# Arduino_S3v3_R3_ftdi.net
KiCad netlist of a schematic drawn in EAGLE
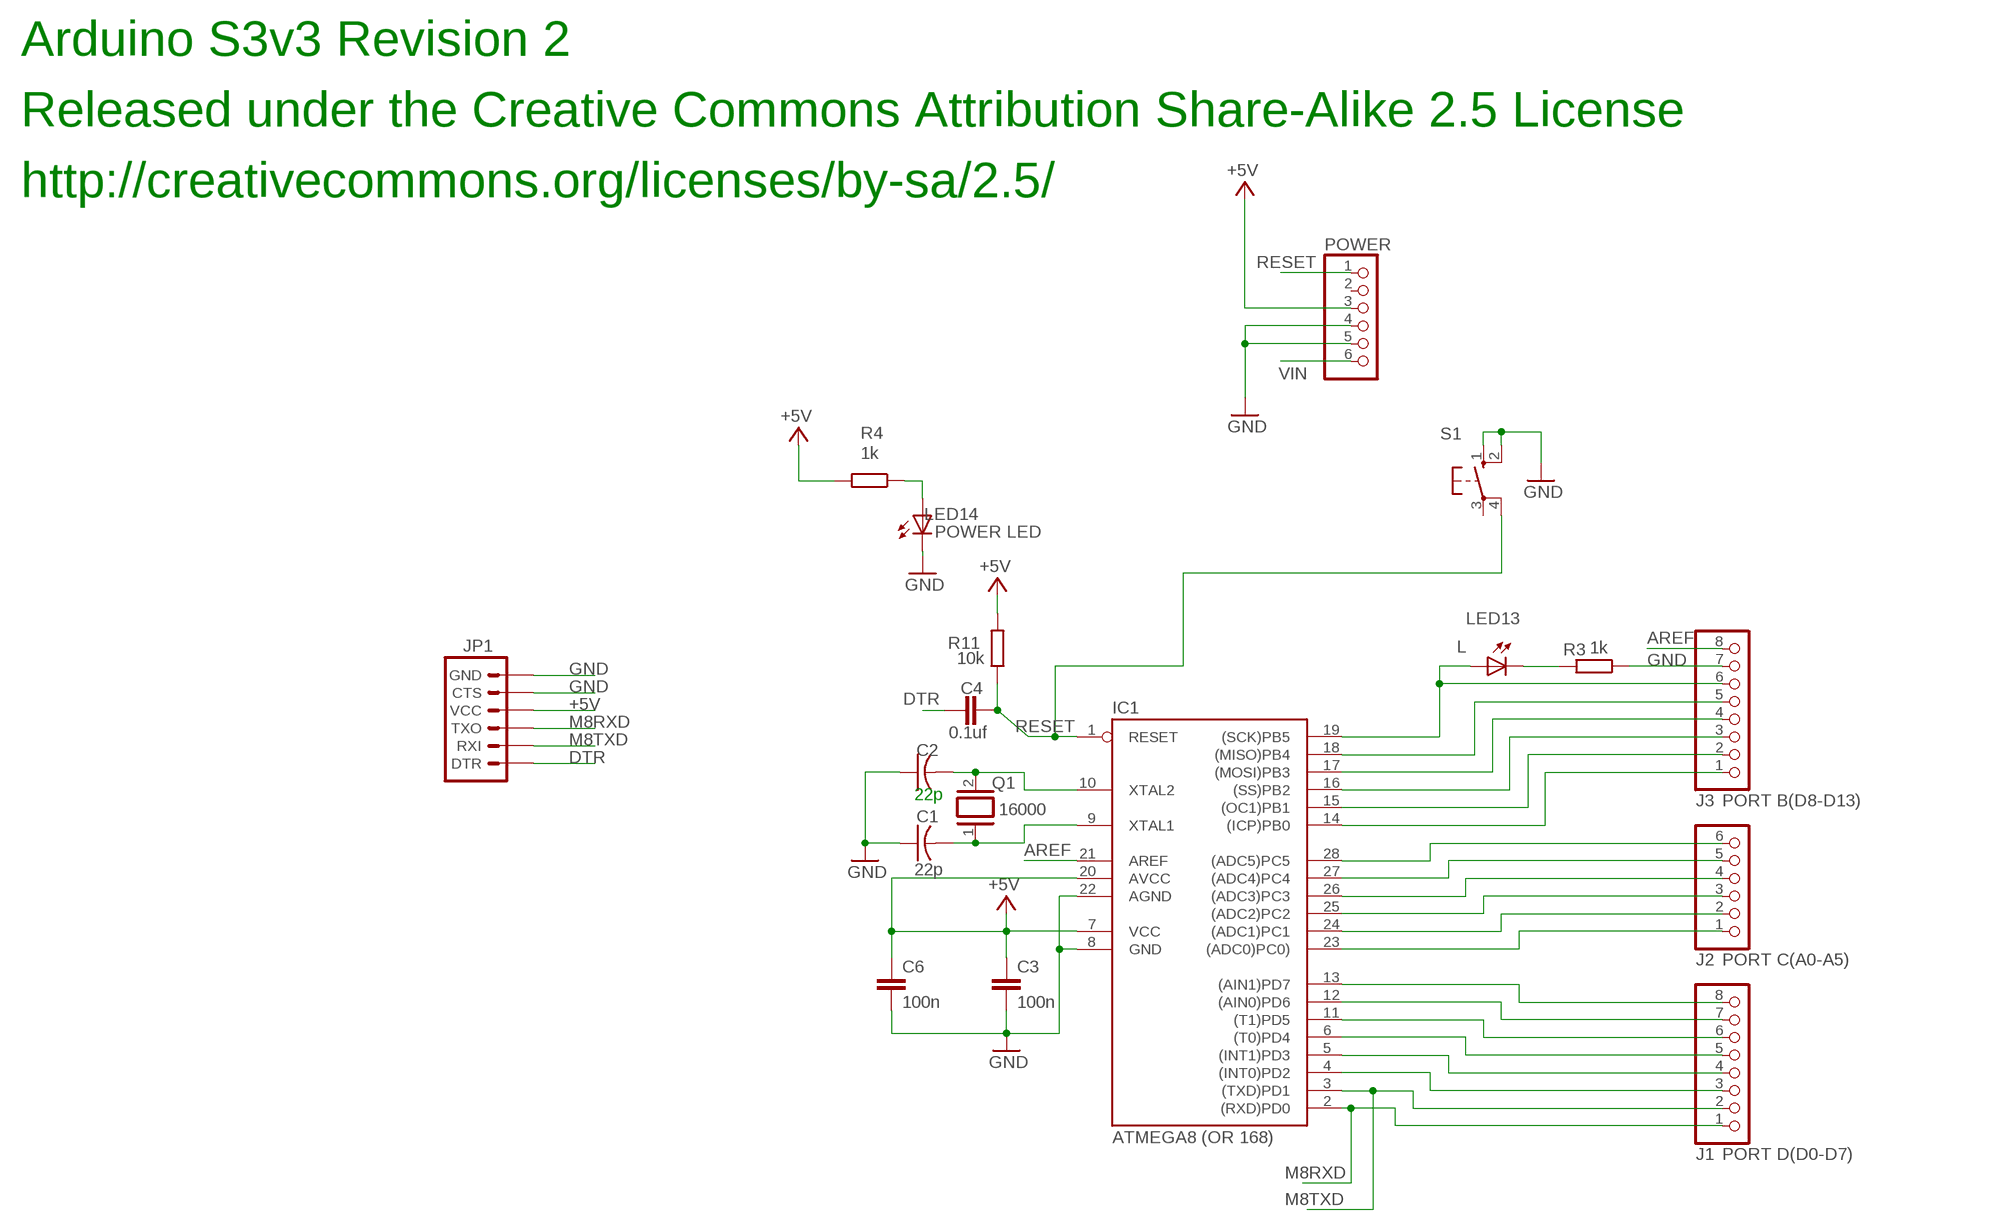
[diagram p0: schematic, sheet 1]

(export (version "E")
  (design (tool "Eeschema 10.0.6"))
  (components
    (comp (ref "C1")
      (value "22p")
      (footprint "eagle-import:C025-024X044")
      (libsource (lib "eagle-import") (part "C-US025-024X044"))
    )
    (comp (ref "C2")
      (value "22p")
      (footprint "eagle-import:C025-024X044")
      (libsource (lib "eagle-import") (part "C-US025-024X044"))
    )
    (comp (ref "C3")
      (value "100n")
      (footprint "eagle-import:C050-025X075")
      (libsource (lib "eagle-import") (part "C-EU050-025X075"))
    )
    (comp (ref "C4")
      (value "0.1uf")
      (footprint "eagle-import:C050-025X075")
      (libsource (lib "eagle-import") (part "C-EU050-025X075"))
    )
    (comp (ref "C6")
      (value "100n")
      (footprint "eagle-import:C050-025X075")
      (libsource (lib "eagle-import") (part "C-EU050-025X075"))
    )
    (comp (ref "IC1")
      (value "ATMEGA8 (OR 168)")
      (footprint "eagle-import:DIL28-3")
      (libsource (lib "eagle-import") (part "AT90S4433P"))
    )
    (comp (ref "J1")
      (value "PORT D(D0-D7)")
      (footprint "eagle-import:1X08")
      (libsource (lib "eagle-import") (part "PINHD-1X8"))
    )
    (comp (ref "J2")
      (value "PORT C(A0-A5)")
      (footprint "eagle-import:1X06")
      (libsource (lib "eagle-import") (part "PINHD-1X6"))
    )
    (comp (ref "J3")
      (value "PORT B(D8-D13)")
      (footprint "eagle-import:1X08")
      (libsource (lib "eagle-import") (part "PINHD-1X8"))
    )
    (comp (ref "JP1")
      (value "ARDUINO_SERIAL_PROGRAMLONGPADS")
      (footprint "eagle-import:1X06_LONGPADS")
      (libsource (lib "eagle-import") (part "ARDUINO_SERIAL_PROGRAMLONGPADS"))
    )
    (comp (ref "LED13")
      (value "L")
      (footprint "eagle-import:LED3MM")
      (libsource (lib "eagle-import") (part "LED3MM"))
    )
    (comp (ref "LED14")
      (value "POWER LED")
      (footprint "eagle-import:LED3MM")
      (libsource (lib "eagle-import") (part "LED3MM"))
    )
    (comp (ref "POWER")
      (value "PINHD-1X6")
      (footprint "eagle-import:1X06")
      (libsource (lib "eagle-import") (part "PINHD-1X6"))
    )
    (comp (ref "Q1")
      (value "16000")
      (footprint "eagle-import:QS")
      (libsource (lib "eagle-import") (part "XTAL/S"))
    )
    (comp (ref "R3")
      (value "1k")
      (footprint "eagle-import:0207_10")
      (libsource (lib "eagle-import") (part "R-EU_0207/10"))
    )
    (comp (ref "R4")
      (value "1k")
      (footprint "eagle-import:0207_10")
      (libsource (lib "eagle-import") (part "R-EU_0207/10"))
    )
    (comp (ref "R11")
      (value "10k")
      (footprint "eagle-import:0207_10")
      (libsource (lib "eagle-import") (part "R-EU_0207/10"))
    )
    (comp (ref "S1")
      (value "10-XX")
      (footprint "eagle-import:B3F-10XX")
      (libsource (lib "eagle-import") (part "10-XX"))
    )
  )
  (nets
    (net (code "1") (name "+5V") (class "Default")
      (node (ref "C3") (pin "1") (pinfunction "1_1") (pintype "passive"))
      (node (ref "C6") (pin "1") (pinfunction "1_1") (pintype "passive"))
      (node (ref "IC1") (pin "20") (pinfunction "AVCC_20") (pintype "power_in"))
      (node (ref "IC1") (pin "7") (pinfunction "VCC_7") (pintype "power_in"))
      (node (ref "JP1") (pin "4") (pinfunction "VCC_4") (pintype "passive"))
      (node (ref "POWER") (pin "3") (pinfunction "3_3") (pintype "passive"))
      (node (ref "R11") (pin "2") (pinfunction "2_2") (pintype "passive"))
      (node (ref "R4") (pin "2") (pinfunction "2_2") (pintype "passive"))
    )
    (net (code "2") (name "/AREF") (class "Default")
      (node (ref "IC1") (pin "21") (pinfunction "AREF_21") (pintype "power_in"))
      (node (ref "J3") (pin "8") (pinfunction "8_8") (pintype "passive"))
    )
    (net (code "3") (name "/DTR") (class "Default")
      (node (ref "C4") (pin "1") (pinfunction "1_1") (pintype "passive"))
      (node (ref "JP1") (pin "1") (pinfunction "DTR_1") (pintype "passive"))
    )
    (net (code "4") (name "/M8RXD") (class "Default")
      (node (ref "IC1") (pin "2") (pinfunction "(RXD)PD0_2") (pintype "bidirectional"))
      (node (ref "J1") (pin "1") (pinfunction "1_1") (pintype "passive"))
      (node (ref "JP1") (pin "3") (pinfunction "TXO_3") (pintype "passive"))
    )
    (net (code "5") (name "/M8TXD") (class "Default")
      (node (ref "IC1") (pin "3") (pinfunction "(TXD)PD1_3") (pintype "bidirectional"))
      (node (ref "J1") (pin "2") (pinfunction "2_2") (pintype "passive"))
      (node (ref "JP1") (pin "2") (pinfunction "RXI_2") (pintype "passive"))
    )
    (net (code "6") (name "/RESET") (class "Default")
      (node (ref "C4") (pin "2") (pinfunction "2_2") (pintype "passive"))
      (node (ref "IC1") (pin "1") (pinfunction "RESET_1") (pintype "input"))
      (node (ref "POWER") (pin "1") (pinfunction "1_1") (pintype "passive"))
      (node (ref "R11") (pin "1") (pinfunction "1_1") (pintype "passive"))
      (node (ref "S1") (pin "4") (pinfunction "P1_4") (pintype "passive"))
    )
    (net (code "7") (name "/VIN") (class "Default")
      (node (ref "POWER") (pin "6") (pinfunction "6_6") (pintype "passive"))
    )
    (net (code "8") (name "GND") (class "Default")
      (node (ref "C1") (pin "1") (pinfunction "1_1") (pintype "passive"))
      (node (ref "C2") (pin "1") (pinfunction "1_1") (pintype "passive"))
      (node (ref "C3") (pin "2") (pinfunction "2_2") (pintype "passive"))
      (node (ref "C6") (pin "2") (pinfunction "2_2") (pintype "passive"))
      (node (ref "IC1") (pin "22") (pinfunction "AGND_22") (pintype "power_in"))
      (node (ref "IC1") (pin "8") (pinfunction "GND_8") (pintype "power_in"))
      (node (ref "J3") (pin "7") (pinfunction "7_7") (pintype "passive"))
      (node (ref "JP1") (pin "5") (pinfunction "CTS_5") (pintype "passive"))
      (node (ref "JP1") (pin "6") (pinfunction "GND_6") (pintype "passive"))
      (node (ref "LED14") (pin "K") (pinfunction "C_K") (pintype "passive"))
      (node (ref "POWER") (pin "4") (pinfunction "4_4") (pintype "passive"))
      (node (ref "POWER") (pin "5") (pinfunction "5_5") (pintype "passive"))
      (node (ref "R3") (pin "1") (pinfunction "1_1") (pintype "passive"))
      (node (ref "S1") (pin "1") (pinfunction "S_1") (pintype "passive"))
      (node (ref "S1") (pin "2") (pinfunction "S1_2") (pintype "passive"))
    )
    (net (code "9") (name "Net-(IC1-(ADC0)PC0))") (class "Default")
      (node (ref "IC1") (pin "23") (pinfunction "(ADC0)PC0)_23") (pintype "bidirectional"))
      (node (ref "J2") (pin "1") (pinfunction "1_1") (pintype "passive"))
    )
    (net (code "10") (name "Net-(IC1-(ADC1)PC1)") (class "Default")
      (node (ref "IC1") (pin "24") (pinfunction "(ADC1)PC1_24") (pintype "bidirectional"))
      (node (ref "J2") (pin "2") (pinfunction "2_2") (pintype "passive"))
    )
    (net (code "11") (name "Net-(IC1-(ADC2)PC2)") (class "Default")
      (node (ref "IC1") (pin "25") (pinfunction "(ADC2)PC2_25") (pintype "bidirectional"))
      (node (ref "J2") (pin "3") (pinfunction "3_3") (pintype "passive"))
    )
    (net (code "12") (name "Net-(IC1-(ADC3)PC3)") (class "Default")
      (node (ref "IC1") (pin "26") (pinfunction "(ADC3)PC3_26") (pintype "bidirectional"))
      (node (ref "J2") (pin "4") (pinfunction "4_4") (pintype "passive"))
    )
    (net (code "13") (name "Net-(IC1-(ADC4)PC4)") (class "Default")
      (node (ref "IC1") (pin "27") (pinfunction "(ADC4)PC4_27") (pintype "bidirectional"))
      (node (ref "J2") (pin "5") (pinfunction "5_5") (pintype "passive"))
    )
    (net (code "14") (name "Net-(IC1-(ADC5)PC5)") (class "Default")
      (node (ref "IC1") (pin "28") (pinfunction "(ADC5)PC5_28") (pintype "bidirectional"))
      (node (ref "J2") (pin "6") (pinfunction "6_6") (pintype "passive"))
    )
    (net (code "15") (name "Net-(IC1-(AIN0)PD6)") (class "Default")
      (node (ref "IC1") (pin "12") (pinfunction "(AIN0)PD6_12") (pintype "bidirectional"))
      (node (ref "J1") (pin "7") (pinfunction "7_7") (pintype "passive"))
    )
    (net (code "16") (name "Net-(IC1-(AIN1)PD7)") (class "Default")
      (node (ref "IC1") (pin "13") (pinfunction "(AIN1)PD7_13") (pintype "bidirectional"))
      (node (ref "J1") (pin "8") (pinfunction "8_8") (pintype "passive"))
    )
    (net (code "17") (name "Net-(IC1-(ICP)PB0)") (class "Default")
      (node (ref "IC1") (pin "14") (pinfunction "(ICP)PB0_14") (pintype "bidirectional"))
      (node (ref "J3") (pin "1") (pinfunction "1_1") (pintype "passive"))
    )
    (net (code "18") (name "Net-(IC1-(INT0)PD2)") (class "Default")
      (node (ref "IC1") (pin "4") (pinfunction "(INT0)PD2_4") (pintype "bidirectional"))
      (node (ref "J1") (pin "3") (pinfunction "3_3") (pintype "passive"))
    )
    (net (code "19") (name "Net-(IC1-(INT1)PD3)") (class "Default")
      (node (ref "IC1") (pin "5") (pinfunction "(INT1)PD3_5") (pintype "bidirectional"))
      (node (ref "J1") (pin "4") (pinfunction "4_4") (pintype "passive"))
    )
    (net (code "20") (name "Net-(IC1-(MISO)PB4)") (class "Default")
      (node (ref "IC1") (pin "18") (pinfunction "(MISO)PB4_18") (pintype "bidirectional"))
      (node (ref "J3") (pin "5") (pinfunction "5_5") (pintype "passive"))
    )
    (net (code "21") (name "Net-(IC1-(MOSI)PB3)") (class "Default")
      (node (ref "IC1") (pin "17") (pinfunction "(MOSI)PB3_17") (pintype "bidirectional"))
      (node (ref "J3") (pin "4") (pinfunction "4_4") (pintype "passive"))
    )
    (net (code "22") (name "Net-(IC1-(OC1)PB1)") (class "Default")
      (node (ref "IC1") (pin "15") (pinfunction "(OC1)PB1_15") (pintype "bidirectional"))
      (node (ref "J3") (pin "2") (pinfunction "2_2") (pintype "passive"))
    )
    (net (code "23") (name "Net-(IC1-(SCK)PB5)") (class "Default")
      (node (ref "IC1") (pin "19") (pinfunction "(SCK)PB5_19") (pintype "bidirectional"))
      (node (ref "J3") (pin "6") (pinfunction "6_6") (pintype "passive"))
      (node (ref "LED13") (pin "A") (pinfunction "A_A") (pintype "passive"))
    )
    (net (code "24") (name "Net-(IC1-(SS)PB2)") (class "Default")
      (node (ref "IC1") (pin "16") (pinfunction "(SS)PB2_16") (pintype "bidirectional"))
      (node (ref "J3") (pin "3") (pinfunction "3_3") (pintype "passive"))
    )
    (net (code "25") (name "Net-(IC1-(T0)PD4)") (class "Default")
      (node (ref "IC1") (pin "6") (pinfunction "(T0)PD4_6") (pintype "bidirectional"))
      (node (ref "J1") (pin "5") (pinfunction "5_5") (pintype "passive"))
    )
    (net (code "26") (name "Net-(IC1-(T1)PD5)") (class "Default")
      (node (ref "IC1") (pin "11") (pinfunction "(T1)PD5_11") (pintype "bidirectional"))
      (node (ref "J1") (pin "6") (pinfunction "6_6") (pintype "passive"))
    )
    (net (code "27") (name "Net-(IC1-XTAL1)") (class "Default")
      (node (ref "C1") (pin "2") (pinfunction "2_2") (pintype "passive"))
      (node (ref "IC1") (pin "9") (pinfunction "XTAL1_9") (pintype "bidirectional"))
      (node (ref "Q1") (pin "1") (pinfunction "1_1") (pintype "passive"))
    )
    (net (code "28") (name "Net-(IC1-XTAL2)") (class "Default")
      (node (ref "C2") (pin "2") (pinfunction "2_2") (pintype "passive"))
      (node (ref "IC1") (pin "10") (pinfunction "XTAL2_10") (pintype "bidirectional"))
      (node (ref "Q1") (pin "2") (pinfunction "2_2") (pintype "passive"))
    )
    (net (code "29") (name "Net-(LED13-C)") (class "Default")
      (node (ref "LED13") (pin "K") (pinfunction "C_K") (pintype "passive"))
      (node (ref "R3") (pin "2") (pinfunction "2_2") (pintype "passive"))
    )
    (net (code "30") (name "Net-(LED14-PadA)") (class "Default")
      (node (ref "LED14") (pin "A") (pinfunction "A_A") (pintype "passive"))
      (node (ref "R4") (pin "1") (pinfunction "1_1") (pintype "passive"))
    )
    (net (code "31") (name "unconnected-(POWER-Pad2)") (class "Default")
      (node (ref "POWER") (pin "2") (pinfunction "2_2") (pintype "passive"))
    )
    (net (code "32") (name "unconnected-(S1-P-Pad3)") (class "Default")
      (node (ref "S1") (pin "3") (pinfunction "P_3") (pintype "passive"))
    )
  )
)
